# development_board.net
KiCad netlist of a schematic drawn in EAGLE
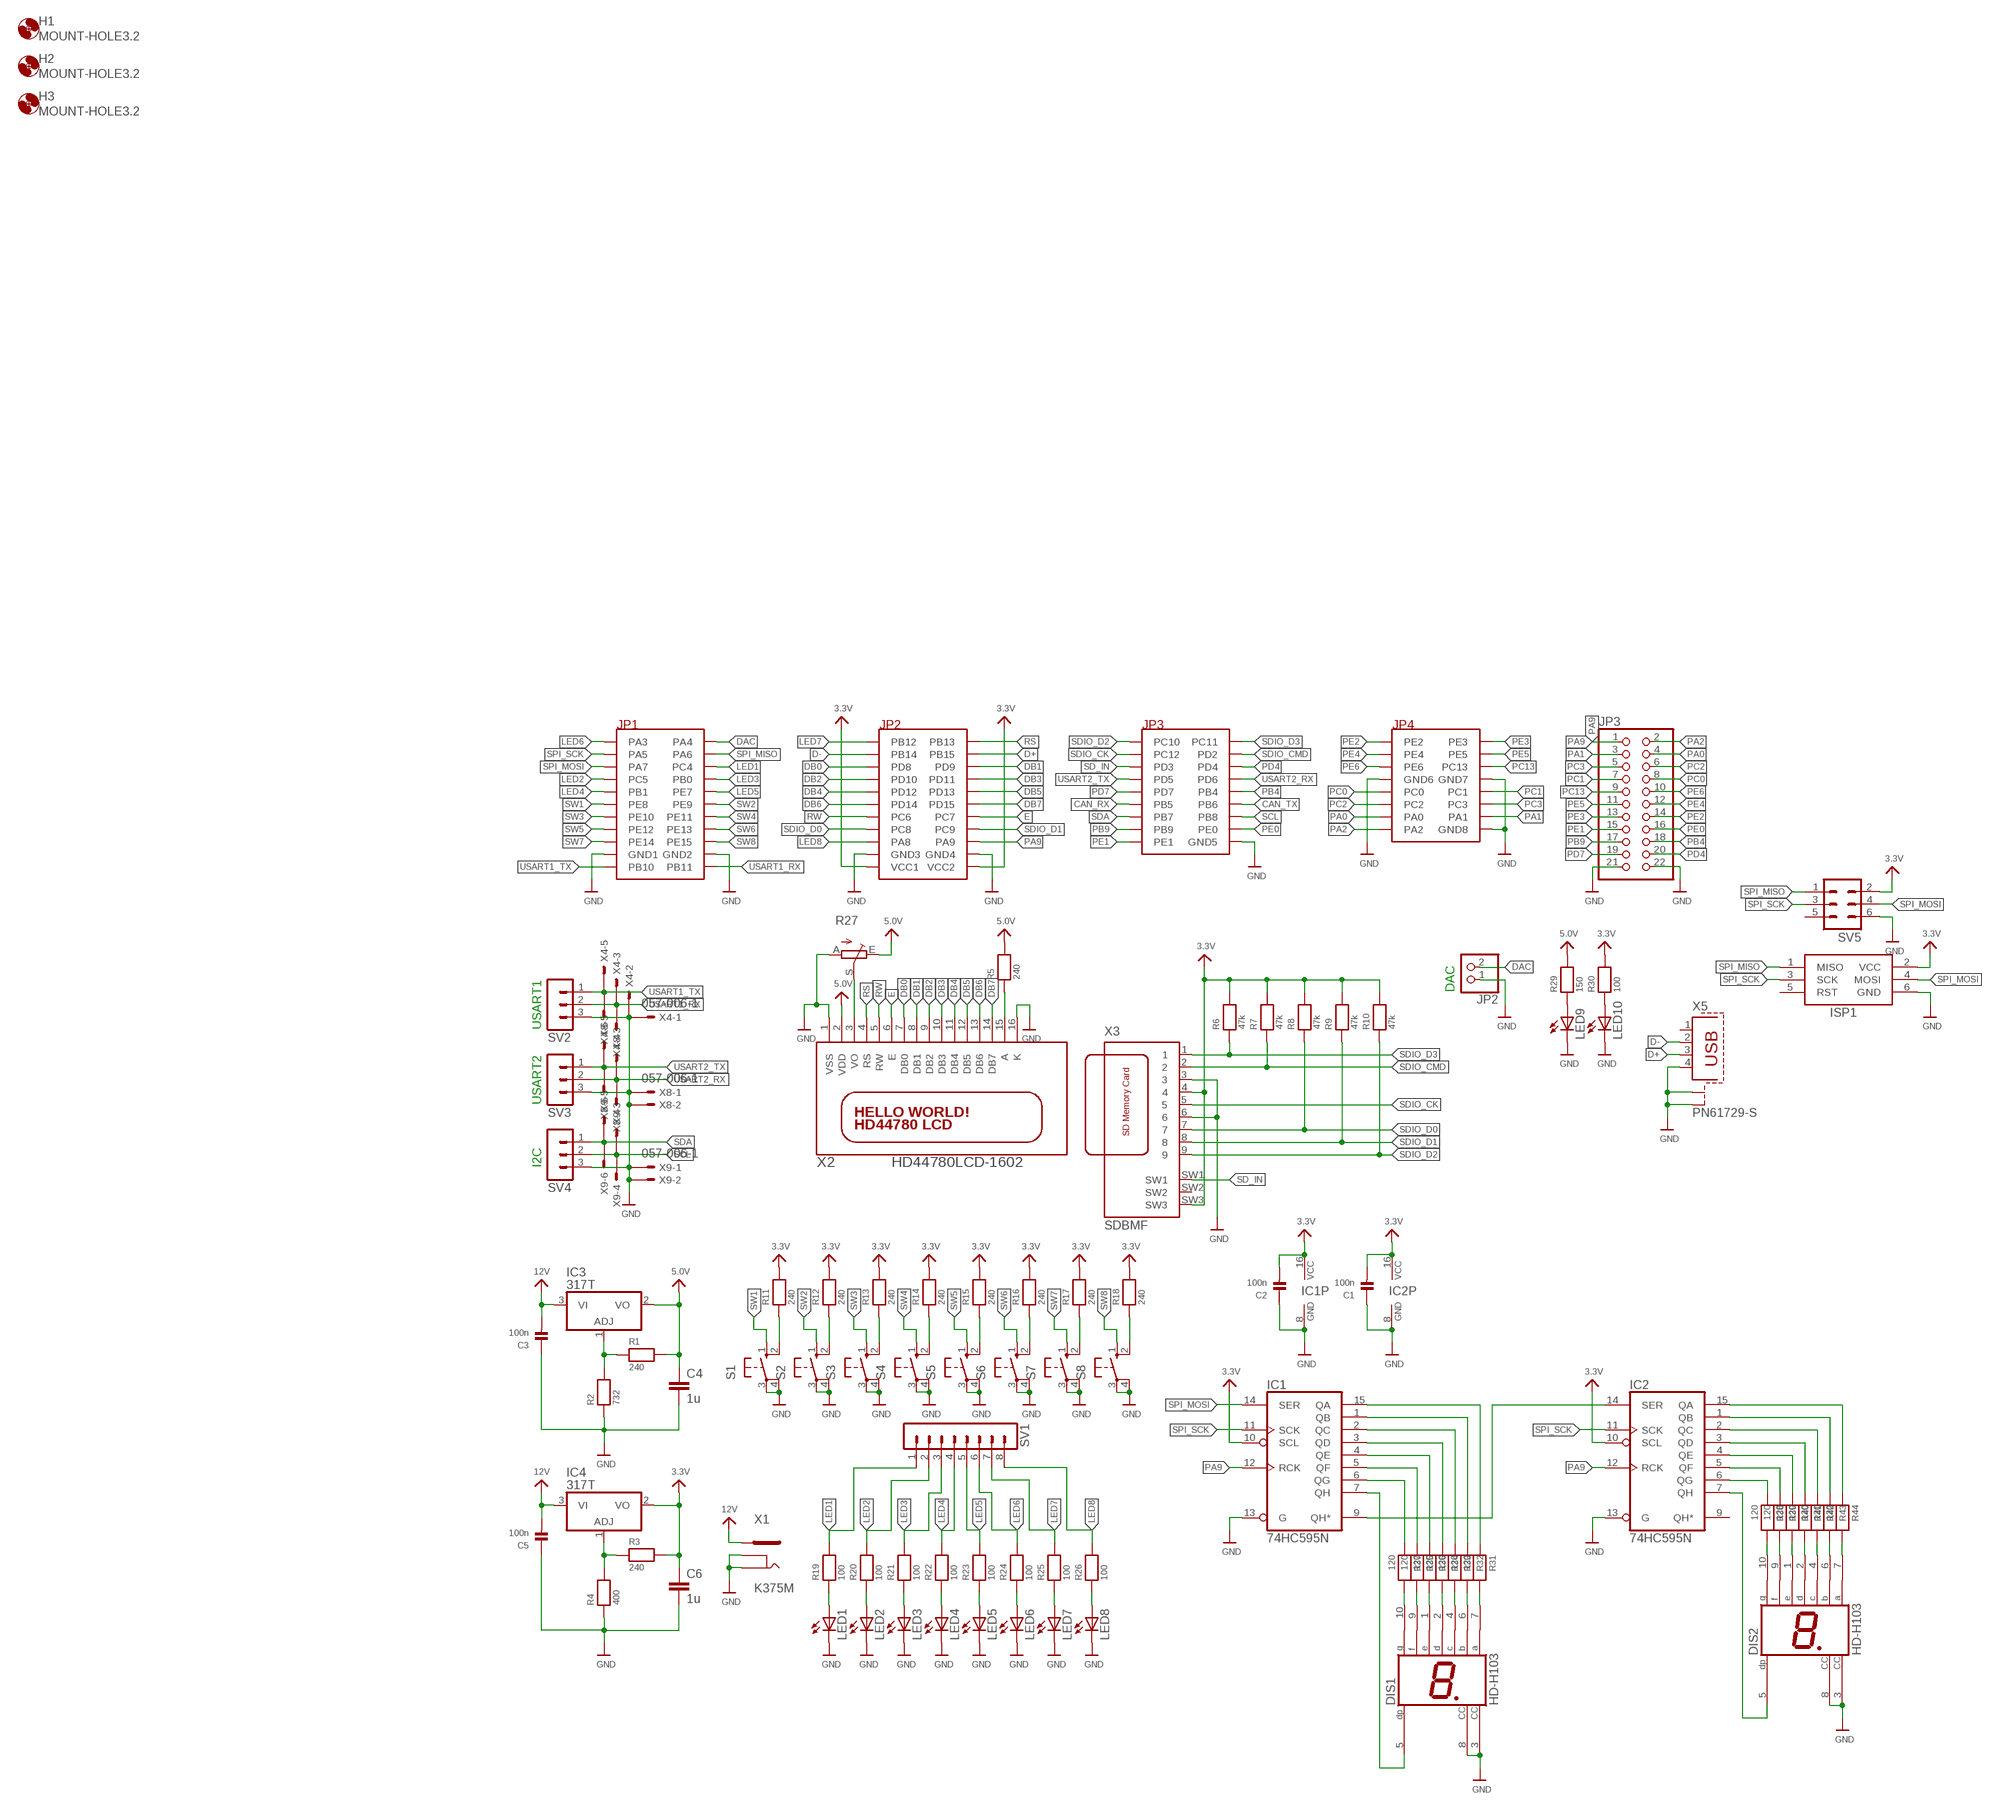
[diagram p0: schematic, sheet 1, part 1 of 2]
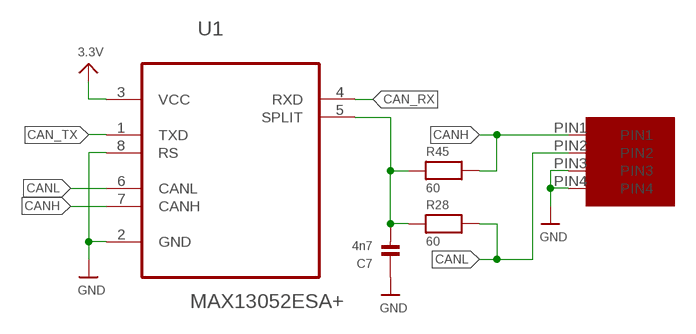
[diagram p1: schematic, sheet 1, part 2 of 2]

(export (version "E")
  (design (tool "Eeschema 10.0.6"))
  (components
    (comp (ref "C1")
      (value "100n")
      (footprint "eagle-import:_0603")
      (libsource (lib "eagle-import") (part "CAP_CERAMIC_0603"))
    )
    (comp (ref "C2")
      (value "100n")
      (footprint "eagle-import:_0603")
      (libsource (lib "eagle-import") (part "CAP_CERAMIC_0603"))
    )
    (comp (ref "C3")
      (value "100n")
      (footprint "eagle-import:_0603")
      (libsource (lib "eagle-import") (part "CAP_CERAMIC_0603"))
    )
    (comp (ref "C4")
      (value "1u")
      (footprint "eagle-import:C050-035X075")
      (libsource (lib "eagle-import") (part "C-EU050-035X075"))
    )
    (comp (ref "C5")
      (value "100n")
      (footprint "eagle-import:_0603")
      (libsource (lib "eagle-import") (part "CAP_CERAMIC_0603"))
    )
    (comp (ref "C6")
      (value "1u")
      (footprint "eagle-import:C050-035X075")
      (libsource (lib "eagle-import") (part "C-EU050-035X075"))
    )
    (comp (ref "C7")
      (value "4n7")
      (footprint "eagle-import:_0603")
      (libsource (lib "eagle-import") (part "CAP_CERAMIC_0603"))
    )
    (comp (ref "DIS1")
      (value "HD-H103")
      (footprint "eagle-import:HDSP-M")
      (libsource (lib "eagle-import") (part "HD-H103"))
    )
    (comp (ref "DIS2")
      (value "HD-H103")
      (footprint "eagle-import:HDSP-M")
      (libsource (lib "eagle-import") (part "HD-H103"))
    )
    (comp (ref "H1")
      (value "MOUNT-HOLE3.2")
      (footprint "eagle-import:3,2")
      (libsource (lib "eagle-import") (part "MOUNT-HOLE3.2"))
    )
    (comp (ref "H2")
      (value "MOUNT-HOLE3.2")
      (footprint "eagle-import:3,2")
      (libsource (lib "eagle-import") (part "MOUNT-HOLE3.2"))
    )
    (comp (ref "H3")
      (value "MOUNT-HOLE3.2")
      (footprint "eagle-import:3,2")
      (libsource (lib "eagle-import") (part "MOUNT-HOLE3.2"))
    )
    (comp (ref "IC1")
      (value "74HC595N")
      (footprint "eagle-import:DIL16")
      (libsource (lib "eagle-import") (part "74595NHC"))
    )
    (comp (ref "IC2")
      (value "74HC595N")
      (footprint "eagle-import:DIL16")
      (libsource (lib "eagle-import") (part "74595NHC"))
    )
    (comp (ref "IC3")
      (value "317T")
      (footprint "eagle-import:TO220H")
      (libsource (lib "eagle-import") (part "317T"))
    )
    (comp (ref "IC4")
      (value "317T")
      (footprint "eagle-import:TO220H")
      (libsource (lib "eagle-import") (part "317T"))
    )
    (comp (ref "ISP1")
      (value "AVRISP-BOX")
      (footprint "eagle-import:AVRISP-BOX")
      (libsource (lib "eagle-import") (part "AVRISP-BOX"))
    )
    (comp (ref "JP2")
      (value "HEADER-1X2ROUND")
      (footprint "eagle-import:1X02_ROUND")
      (libsource (lib "eagle-import") (part "HEADER-1X2ROUND"))
    )
    (comp (ref "JP3")
      (value "PINHD-2X11")
      (footprint "eagle-import:2X11")
      (libsource (lib "eagle-import") (part "PINHD-2X11"))
    )
    (comp (ref "LED1")
      (value "LED5MM")
      (footprint "eagle-import:LED5MM")
      (libsource (lib "eagle-import") (part "LED5MM"))
    )
    (comp (ref "LED2")
      (value "LED5MM")
      (footprint "eagle-import:LED5MM")
      (libsource (lib "eagle-import") (part "LED5MM"))
    )
    (comp (ref "LED3")
      (value "LED5MM")
      (footprint "eagle-import:LED5MM")
      (libsource (lib "eagle-import") (part "LED5MM"))
    )
    (comp (ref "LED4")
      (value "LED5MM")
      (footprint "eagle-import:LED5MM")
      (libsource (lib "eagle-import") (part "LED5MM"))
    )
    (comp (ref "LED5")
      (value "LED5MM")
      (footprint "eagle-import:LED5MM")
      (libsource (lib "eagle-import") (part "LED5MM"))
    )
    (comp (ref "LED6")
      (value "LED5MM")
      (footprint "eagle-import:LED5MM")
      (libsource (lib "eagle-import") (part "LED5MM"))
    )
    (comp (ref "LED7")
      (value "LED5MM")
      (footprint "eagle-import:LED5MM")
      (libsource (lib "eagle-import") (part "LED5MM"))
    )
    (comp (ref "LED8")
      (value "LED5MM")
      (footprint "eagle-import:LED5MM")
      (libsource (lib "eagle-import") (part "LED5MM"))
    )
    (comp (ref "LED9")
      (value "LED3MM")
      (footprint "eagle-import:LED3MM")
      (libsource (lib "eagle-import") (part "led_LED3MM"))
    )
    (comp (ref "LED10")
      (value "LED3MM")
      (footprint "eagle-import:LED3MM")
      (libsource (lib "eagle-import") (part "led_LED3MM"))
    )
    (comp (ref "R1")
      (value "240")
      (footprint "eagle-import:_0603")
      (libsource (lib "eagle-import") (part "RESISTOR_0603"))
    )
    (comp (ref "R2")
      (value "732")
      (footprint "eagle-import:_0603")
      (libsource (lib "eagle-import") (part "RESISTOR_0603"))
    )
    (comp (ref "R3")
      (value "240")
      (footprint "eagle-import:_0603")
      (libsource (lib "eagle-import") (part "RESISTOR_0603"))
    )
    (comp (ref "R4")
      (value "400")
      (footprint "eagle-import:_0603")
      (libsource (lib "eagle-import") (part "RESISTOR_0603"))
    )
    (comp (ref "R5")
      (value "240")
      (footprint "eagle-import:_0603")
      (libsource (lib "eagle-import") (part "RESISTOR_0603"))
    )
    (comp (ref "R6")
      (value "47k")
      (footprint "eagle-import:_0603")
      (libsource (lib "eagle-import") (part "RESISTOR_0603"))
    )
    (comp (ref "R7")
      (value "47k")
      (footprint "eagle-import:_0603")
      (libsource (lib "eagle-import") (part "RESISTOR_0603"))
    )
    (comp (ref "R8")
      (value "47k")
      (footprint "eagle-import:_0603")
      (libsource (lib "eagle-import") (part "RESISTOR_0603"))
    )
    (comp (ref "R9")
      (value "47k")
      (footprint "eagle-import:_0603")
      (libsource (lib "eagle-import") (part "RESISTOR_0603"))
    )
    (comp (ref "R10")
      (value "47k")
      (footprint "eagle-import:_0603")
      (libsource (lib "eagle-import") (part "RESISTOR_0603"))
    )
    (comp (ref "R11")
      (value "240")
      (footprint "eagle-import:_0603")
      (libsource (lib "eagle-import") (part "RESISTOR_0603"))
    )
    (comp (ref "R12")
      (value "240")
      (footprint "eagle-import:_0603")
      (libsource (lib "eagle-import") (part "RESISTOR_0603"))
    )
    (comp (ref "R13")
      (value "240")
      (footprint "eagle-import:_0603")
      (libsource (lib "eagle-import") (part "RESISTOR_0603"))
    )
    (comp (ref "R14")
      (value "240")
      (footprint "eagle-import:_0603")
      (libsource (lib "eagle-import") (part "RESISTOR_0603"))
    )
    (comp (ref "R15")
      (value "240")
      (footprint "eagle-import:_0603")
      (libsource (lib "eagle-import") (part "RESISTOR_0603"))
    )
    (comp (ref "R16")
      (value "240")
      (footprint "eagle-import:_0603")
      (libsource (lib "eagle-import") (part "RESISTOR_0603"))
    )
    (comp (ref "R17")
      (value "240")
      (footprint "eagle-import:_0603")
      (libsource (lib "eagle-import") (part "RESISTOR_0603"))
    )
    (comp (ref "R18")
      (value "240")
      (footprint "eagle-import:_0603")
      (libsource (lib "eagle-import") (part "RESISTOR_0603"))
    )
    (comp (ref "R19")
      (value "100")
      (footprint "eagle-import:_0603")
      (libsource (lib "eagle-import") (part "RESISTOR_0603"))
    )
    (comp (ref "R20")
      (value "100")
      (footprint "eagle-import:_0603")
      (libsource (lib "eagle-import") (part "RESISTOR_0603"))
    )
    (comp (ref "R21")
      (value "100")
      (footprint "eagle-import:_0603")
      (libsource (lib "eagle-import") (part "RESISTOR_0603"))
    )
    (comp (ref "R22")
      (value "100")
      (footprint "eagle-import:_0603")
      (libsource (lib "eagle-import") (part "RESISTOR_0603"))
    )
    (comp (ref "R23")
      (value "100")
      (footprint "eagle-import:_0603")
      (libsource (lib "eagle-import") (part "RESISTOR_0603"))
    )
    (comp (ref "R24")
      (value "100")
      (footprint "eagle-import:_0603")
      (libsource (lib "eagle-import") (part "RESISTOR_0603"))
    )
    (comp (ref "R25")
      (value "100")
      (footprint "eagle-import:_0603")
      (libsource (lib "eagle-import") (part "RESISTOR_0603"))
    )
    (comp (ref "R26")
      (value "100")
      (footprint "eagle-import:_0603")
      (libsource (lib "eagle-import") (part "RESISTOR_0603"))
    )
    (comp (ref "R27")
      (value "TRIM_EU-RJ9W")
      (footprint "eagle-import:RJ9W")
      (libsource (lib "eagle-import") (part "TRIM_EU-RJ9W"))
    )
    (comp (ref "R28")
      (value "60")
      (footprint "eagle-import:_0603")
      (libsource (lib "eagle-import") (part "RESISTOR_0603"))
    )
    (comp (ref "R29")
      (value "150")
      (footprint "eagle-import:_0603")
      (libsource (lib "eagle-import") (part "RESISTOR_0603"))
    )
    (comp (ref "R30")
      (value "100")
      (footprint "eagle-import:_0603")
      (libsource (lib "eagle-import") (part "RESISTOR_0603"))
    )
    (comp (ref "R31")
      (value "120")
      (footprint "eagle-import:_0603")
      (libsource (lib "eagle-import") (part "RESISTOR_0603"))
    )
    (comp (ref "R32")
      (value "120")
      (footprint "eagle-import:_0603")
      (libsource (lib "eagle-import") (part "RESISTOR_0603"))
    )
    (comp (ref "R33")
      (value "120")
      (footprint "eagle-import:_0603")
      (libsource (lib "eagle-import") (part "RESISTOR_0603"))
    )
    (comp (ref "R34")
      (value "120")
      (footprint "eagle-import:_0603")
      (libsource (lib "eagle-import") (part "RESISTOR_0603"))
    )
    (comp (ref "R35")
      (value "120")
      (footprint "eagle-import:_0603")
      (libsource (lib "eagle-import") (part "RESISTOR_0603"))
    )
    (comp (ref "R36")
      (value "120")
      (footprint "eagle-import:_0603")
      (libsource (lib "eagle-import") (part "RESISTOR_0603"))
    )
    (comp (ref "R37")
      (value "120")
      (footprint "eagle-import:_0603")
      (libsource (lib "eagle-import") (part "RESISTOR_0603"))
    )
    (comp (ref "R38")
      (value "120")
      (footprint "eagle-import:_0603")
      (libsource (lib "eagle-import") (part "RESISTOR_0603"))
    )
    (comp (ref "R39")
      (value "120")
      (footprint "eagle-import:_0603")
      (libsource (lib "eagle-import") (part "RESISTOR_0603"))
    )
    (comp (ref "R40")
      (value "120")
      (footprint "eagle-import:_0603")
      (libsource (lib "eagle-import") (part "RESISTOR_0603"))
    )
    (comp (ref "R41")
      (value "120")
      (footprint "eagle-import:_0603")
      (libsource (lib "eagle-import") (part "RESISTOR_0603"))
    )
    (comp (ref "R42")
      (value "120")
      (footprint "eagle-import:_0603")
      (libsource (lib "eagle-import") (part "RESISTOR_0603"))
    )
    (comp (ref "R43")
      (value "120")
      (footprint "eagle-import:_0603")
      (libsource (lib "eagle-import") (part "RESISTOR_0603"))
    )
    (comp (ref "R44")
      (value "120")
      (footprint "eagle-import:_0603")
      (libsource (lib "eagle-import") (part "RESISTOR_0603"))
    )
    (comp (ref "R45")
      (value "60")
      (footprint "eagle-import:_0603")
      (libsource (lib "eagle-import") (part "RESISTOR_0603"))
    )
    (comp (ref "S1")
      (value "10-XX")
      (footprint "eagle-import:B3F-10XX")
      (fields (field (name "MPN") "B3F-1000"))
      (libsource (lib "eagle-import") (part "10-XX"))
    )
    (comp (ref "S2")
      (value "10-XX")
      (footprint "eagle-import:B3F-10XX")
      (fields (field (name "MPN") "B3F-1000"))
      (libsource (lib "eagle-import") (part "10-XX"))
    )
    (comp (ref "S3")
      (value "10-XX")
      (footprint "eagle-import:B3F-10XX")
      (fields (field (name "MPN") "B3F-1000"))
      (libsource (lib "eagle-import") (part "10-XX"))
    )
    (comp (ref "S4")
      (value "10-XX")
      (footprint "eagle-import:B3F-10XX")
      (fields (field (name "MPN") "B3F-1000"))
      (libsource (lib "eagle-import") (part "10-XX"))
    )
    (comp (ref "S5")
      (value "10-XX")
      (footprint "eagle-import:B3F-10XX")
      (fields (field (name "MPN") "B3F-1000"))
      (libsource (lib "eagle-import") (part "10-XX"))
    )
    (comp (ref "S6")
      (value "10-XX")
      (footprint "eagle-import:B3F-10XX")
      (fields (field (name "MPN") "B3F-1000"))
      (libsource (lib "eagle-import") (part "10-XX"))
    )
    (comp (ref "S7")
      (value "10-XX")
      (footprint "eagle-import:B3F-10XX")
      (fields (field (name "MPN") "B3F-1000"))
      (libsource (lib "eagle-import") (part "10-XX"))
    )
    (comp (ref "S8")
      (value "10-XX")
      (footprint "eagle-import:B3F-10XX")
      (fields (field (name "MPN") "B3F-1000"))
      (libsource (lib "eagle-import") (part "10-XX"))
    )
    (comp (ref "SV1")
      (value "MA08-1")
      (footprint "eagle-import:MA08-1")
      (libsource (lib "eagle-import") (part "MA08-1"))
    )
    (comp (ref "SV2")
      (value "MA03-1")
      (footprint "eagle-import:MA03-1")
      (libsource (lib "eagle-import") (part "MA03-1"))
    )
    (comp (ref "SV3")
      (value "MA03-1")
      (footprint "eagle-import:MA03-1")
      (libsource (lib "eagle-import") (part "MA03-1"))
    )
    (comp (ref "SV4")
      (value "MA03-1")
      (footprint "eagle-import:MA03-1")
      (libsource (lib "eagle-import") (part "MA03-1"))
    )
    (comp (ref "SV5")
      (value "MA03-2")
      (footprint "eagle-import:MA03-2")
      (libsource (lib "eagle-import") (part "MA03-2"))
    )
    (comp (ref "U$1")
      (value "CPU-BOARD")
      (footprint "eagle-import:CPU-BOARD-JP1")
      (libsource (lib "eagle-import") (part "CPU-BOARD"))
    )
    (comp (ref "U$57")
      (value "MICROFIT4")
      (footprint "eagle-import:MICROFIT4SOCK")
      (libsource (lib "eagle-import") (part "MICROFIT4"))
    )
    (comp (ref "U1")
      (value "MAX13052ESA+")
      (footprint "eagle-import:SOIC127P600X175-8N")
      (libsource (lib "eagle-import") (part "MAX13052ESA+"))
    )
    (comp (ref "X1")
      (value "K375M")
      (footprint "eagle-import:K375M")
      (libsource (lib "eagle-import") (part "K375M"))
    )
    (comp (ref "X2")
      (value "HD44780LCD-1602")
      (footprint "eagle-import:LCD1602")
      (libsource (lib "eagle-import") (part "HD44780LCD-1602"))
    )
    (comp (ref "X3")
      (value "SDBMF")
      (footprint "eagle-import:SDBMF-009XXBXX2")
      (libsource (lib "eagle-import") (part "SDBMF"))
    )
    (comp (ref "X4")
      (value "057-006-1")
      (footprint "eagle-import:057-006-1")
      (fields (field (name "OC_FARNELL") "unknown") (field (name "OC_NEWARK") "unknown"))
      (libsource (lib "eagle-import") (part "057-006-1"))
    )
    (comp (ref "X5")
      (value "PN61729-S")
      (footprint "eagle-import:PN61729-S")
      (libsource (lib "eagle-import") (part "PN61729-S"))
    )
    (comp (ref "X8")
      (value "057-006-1")
      (footprint "eagle-import:057-006-1")
      (fields (field (name "OC_FARNELL") "unknown") (field (name "OC_NEWARK") "unknown"))
      (libsource (lib "eagle-import") (part "057-006-1"))
    )
    (comp (ref "X9")
      (value "057-006-1")
      (footprint "eagle-import:057-006-1")
      (fields (field (name "OC_FARNELL") "unknown") (field (name "OC_NEWARK") "unknown"))
      (libsource (lib "eagle-import") (part "057-006-1"))
    )
  )
  (nets
    (net (code "1") (name "3.3V") (class "Default")
      (node (ref "C1") (pin "2") (pinfunction "P$2_2") (pintype "passive"))
      (node (ref "C2") (pin "2") (pinfunction "P$2_2") (pintype "passive"))
      (node (ref "C6") (pin "1") (pinfunction "1_1") (pintype "passive"))
      (node (ref "IC1") (pin "10") (pinfunction "SCL_10") (pintype "input"))
      (node (ref "IC1") (pin "16") (pinfunction "VCC_16") (pintype "power_in"))
      (node (ref "IC2") (pin "10") (pinfunction "SCL_10") (pintype "input"))
      (node (ref "IC2") (pin "16") (pinfunction "VCC_16") (pintype "power_in"))
      (node (ref "IC4") (pin "2") (pinfunction "VO_2") (pintype "passive"))
      (node (ref "ISP1") (pin "2") (pinfunction "VCC_2") (pintype "power_in"))
      (node (ref "R10") (pin "2") (pinfunction "2_2") (pintype "passive"))
      (node (ref "R11") (pin "2") (pinfunction "2_2") (pintype "passive"))
      (node (ref "R12") (pin "2") (pinfunction "2_2") (pintype "passive"))
      (node (ref "R13") (pin "2") (pinfunction "2_2") (pintype "passive"))
      (node (ref "R14") (pin "2") (pinfunction "2_2") (pintype "passive"))
      (node (ref "R15") (pin "2") (pinfunction "2_2") (pintype "passive"))
      (node (ref "R16") (pin "2") (pinfunction "2_2") (pintype "passive"))
      (node (ref "R17") (pin "2") (pinfunction "2_2") (pintype "passive"))
      (node (ref "R18") (pin "2") (pinfunction "2_2") (pintype "passive"))
      (node (ref "R3") (pin "2") (pinfunction "2_2") (pintype "passive"))
      (node (ref "R30") (pin "2") (pinfunction "2_2") (pintype "passive"))
      (node (ref "R6") (pin "2") (pinfunction "2_2") (pintype "passive"))
      (node (ref "R7") (pin "2") (pinfunction "2_2") (pintype "passive"))
      (node (ref "R8") (pin "2") (pinfunction "2_2") (pintype "passive"))
      (node (ref "R9") (pin "2") (pinfunction "2_2") (pintype "passive"))
      (node (ref "SV5") (pin "2") (pinfunction "2_2") (pintype "passive"))
      (node (ref "U$1") (pin "P$43") (pinfunction "VCC1_P$43") (pintype "bidirectional"))
      (node (ref "U$1") (pin "P$44") (pinfunction "VCC2_P$44") (pintype "bidirectional"))
      (node (ref "U1") (pin "3") (pinfunction "VCC_3") (pintype "power_in"))
      (node (ref "X3") (pin "4") (pinfunction "4_4") (pintype "passive"))
      (node (ref "X3") (pin "SW3") (pinfunction "SW3_SW3") (pintype "passive"))
    )
    (net (code "2") (name "5.0V") (class "Default")
      (node (ref "C4") (pin "1") (pinfunction "1_1") (pintype "passive"))
      (node (ref "IC3") (pin "2") (pinfunction "VO_2") (pintype "passive"))
      (node (ref "R1") (pin "2") (pinfunction "2_2") (pintype "passive"))
      (node (ref "R27") (pin "E") (pinfunction "E_E") (pintype "passive"))
      (node (ref "R29") (pin "2") (pinfunction "2_2") (pintype "passive"))
      (node (ref "R5") (pin "2") (pinfunction "2_2") (pintype "passive"))
      (node (ref "X2") (pin "2") (pinfunction "VDD_2") (pintype "power_in"))
    )
    (net (code "3") (name "12V") (class "Default")
      (node (ref "C3") (pin "2") (pinfunction "P$2_2") (pintype "passive"))
      (node (ref "C5") (pin "2") (pinfunction "P$2_2") (pintype "passive"))
      (node (ref "IC3") (pin "3") (pinfunction "VI_3") (pintype "input"))
      (node (ref "IC4") (pin "3") (pinfunction "VI_3") (pintype "input"))
      (node (ref "X1") (pin "1") (pinfunction "1_1") (pintype "passive"))
    )
    (net (code "4") (name "CANH") (class "Default")
      (node (ref "R45") (pin "2") (pinfunction "2_2") (pintype "passive"))
      (node (ref "U$57") (pin "PIN1") (pinfunction "PIN1_PIN1") (pintype "bidirectional"))
      (node (ref "U1") (pin "7") (pinfunction "CANH_7") (pintype "input"))
    )
    (net (code "5") (name "CANL") (class "Default")
      (node (ref "R28") (pin "2") (pinfunction "2_2") (pintype "passive"))
      (node (ref "U$57") (pin "PIN2") (pinfunction "PIN2_PIN2") (pintype "bidirectional"))
      (node (ref "U1") (pin "6") (pinfunction "CANL_6") (pintype "input"))
    )
    (net (code "6") (name "CAN_RX") (class "Default")
      (node (ref "U$1") (pin "P$55") (pinfunction "PB5_P$55") (pintype "bidirectional"))
      (node (ref "U1") (pin "4") (pinfunction "RXD_4") (pintype "output"))
    )
    (net (code "7") (name "CAN_TX") (class "Default")
      (node (ref "U$1") (pin "P$56") (pinfunction "PB6_P$56") (pintype "bidirectional"))
      (node (ref "U1") (pin "1") (pinfunction "TXD_1") (pintype "input"))
    )
    (net (code "8") (name "D+") (class "Default")
      (node (ref "U$1") (pin "P$26") (pinfunction "PB15_P$26") (pintype "bidirectional"))
      (node (ref "X5") (pin "3") (pinfunction "3_3") (pintype "passive"))
    )
    (net (code "9") (name "D-") (class "Default")
      (node (ref "U$1") (pin "P$25") (pinfunction "PB14_P$25") (pintype "bidirectional"))
      (node (ref "X5") (pin "2") (pinfunction "2_2") (pintype "passive"))
    )
    (net (code "10") (name "DAC") (class "Default")
      (node (ref "JP2") (pin "2") (pinfunction "2_2") (pintype "passive"))
      (node (ref "U$1") (pin "P$2") (pinfunction "PA4_P$2") (pintype "bidirectional"))
    )
    (net (code "11") (name "DB0") (class "Default")
      (node (ref "U$1") (pin "P$27") (pinfunction "PD8_P$27") (pintype "bidirectional"))
      (node (ref "X2") (pin "7") (pinfunction "DB0_7") (pintype "bidirectional"))
    )
    (net (code "12") (name "DB1") (class "Default")
      (node (ref "U$1") (pin "P$28") (pinfunction "PD9_P$28") (pintype "bidirectional"))
      (node (ref "X2") (pin "8") (pinfunction "DB1_8") (pintype "bidirectional"))
    )
    (net (code "13") (name "DB2") (class "Default")
      (node (ref "U$1") (pin "P$29") (pinfunction "PD10_P$29") (pintype "bidirectional"))
      (node (ref "X2") (pin "9") (pinfunction "DB2_9") (pintype "bidirectional"))
    )
    (net (code "14") (name "DB3") (class "Default")
      (node (ref "U$1") (pin "P$30") (pinfunction "PD11_P$30") (pintype "bidirectional"))
      (node (ref "X2") (pin "10") (pinfunction "DB3_10") (pintype "bidirectional"))
    )
    (net (code "15") (name "DB4") (class "Default")
      (node (ref "U$1") (pin "P$31") (pinfunction "PD12_P$31") (pintype "bidirectional"))
      (node (ref "X2") (pin "11") (pinfunction "DB4_11") (pintype "bidirectional"))
    )
    (net (code "16") (name "DB5") (class "Default")
      (node (ref "U$1") (pin "P$32") (pinfunction "PD13_P$32") (pintype "bidirectional"))
      (node (ref "X2") (pin "12") (pinfunction "DB5_12") (pintype "bidirectional"))
    )
    (net (code "17") (name "DB6") (class "Default")
      (node (ref "U$1") (pin "P$33") (pinfunction "PD14_P$33") (pintype "bidirectional"))
      (node (ref "X2") (pin "13") (pinfunction "DB6_13") (pintype "bidirectional"))
    )
    (net (code "18") (name "DB7") (class "Default")
      (node (ref "U$1") (pin "P$34") (pinfunction "PD15_P$34") (pintype "bidirectional"))
      (node (ref "X2") (pin "14") (pinfunction "DB7_14") (pintype "bidirectional"))
    )
    (net (code "19") (name "E") (class "Default")
      (node (ref "U$1") (pin "P$36") (pinfunction "PC7_P$36") (pintype "bidirectional"))
      (node (ref "X2") (pin "6") (pinfunction "E_6") (pintype "input"))
    )
    (net (code "20") (name "GND") (class "Default")
      (node (ref "C1") (pin "1") (pinfunction "P$1_1") (pintype "passive"))
      (node (ref "C2") (pin "1") (pinfunction "P$1_1") (pintype "passive"))
      (node (ref "C3") (pin "1") (pinfunction "P$1_1") (pintype "passive"))
      (node (ref "C4") (pin "2") (pinfunction "2_2") (pintype "passive"))
      (node (ref "C5") (pin "1") (pinfunction "P$1_1") (pintype "passive"))
      (node (ref "C6") (pin "2") (pinfunction "2_2") (pintype "passive"))
      (node (ref "C7") (pin "1") (pinfunction "P$1_1") (pintype "passive"))
      (node (ref "DIS1") (pin "3") (pinfunction "CC_3") (pintype "passive"))
      (node (ref "DIS1") (pin "8") (pinfunction "CC_8") (pintype "passive"))
      (node (ref "DIS2") (pin "3") (pinfunction "CC_3") (pintype "passive"))
      (node (ref "DIS2") (pin "8") (pinfunction "CC_8") (pintype "passive"))
      (node (ref "IC1") (pin "13") (pinfunction "G_13") (pintype "input"))
      (node (ref "IC1") (pin "8") (pinfunction "GND_8") (pintype "power_in"))
      (node (ref "IC2") (pin "13") (pinfunction "G_13") (pintype "input"))
      (node (ref "IC2") (pin "8") (pinfunction "GND_8") (pintype "power_in"))
      (node (ref "ISP1") (pin "6") (pinfunction "GND_6") (pintype "power_in"))
      (node (ref "JP2") (pin "1") (pinfunction "1_1") (pintype "passive"))
      (node (ref "JP3") (pin "21") (pinfunction "21_21") (pintype "passive"))
      (node (ref "JP3") (pin "22") (pinfunction "22_22") (pintype "passive"))
      (node (ref "LED1") (pin "K") (pinfunction "C_K") (pintype "passive"))
      (node (ref "LED10") (pin "K") (pinfunction "C_K") (pintype "passive"))
      (node (ref "LED2") (pin "K") (pinfunction "C_K") (pintype "passive"))
      (node (ref "LED3") (pin "K") (pinfunction "C_K") (pintype "passive"))
      (node (ref "LED4") (pin "K") (pinfunction "C_K") (pintype "passive"))
      (node (ref "LED5") (pin "K") (pinfunction "C_K") (pintype "passive"))
      (node (ref "LED6") (pin "K") (pinfunction "C_K") (pintype "passive"))
      (node (ref "LED7") (pin "K") (pinfunction "C_K") (pintype "passive"))
      (node (ref "LED8") (pin "K") (pinfunction "C_K") (pintype "passive"))
      (node (ref "LED9") (pin "K") (pinfunction "C_K") (pintype "passive"))
      (node (ref "R2") (pin "1") (pinfunction "1_1") (pintype "passive"))
      (node (ref "R27") (pin "A") (pinfunction "A_A") (pintype "passive"))
      (node (ref "R4") (pin "1") (pinfunction "1_1") (pintype "passive"))
      (node (ref "S1") (pin "3") (pinfunction "P_3") (pintype "passive"))
      (node (ref "S1") (pin "4") (pinfunction "P1_4") (pintype "passive"))
      (node (ref "S2") (pin "3") (pinfunction "P_3") (pintype "passive"))
      (node (ref "S2") (pin "4") (pinfunction "P1_4") (pintype "passive"))
      (node (ref "S3") (pin "3") (pinfunction "P_3") (pintype "passive"))
      (node (ref "S3") (pin "4") (pinfunction "P1_4") (pintype "passive"))
      (node (ref "S4") (pin "3") (pinfunction "P_3") (pintype "passive"))
      (node (ref "S4") (pin "4") (pinfunction "P1_4") (pintype "passive"))
      (node (ref "S5") (pin "3") (pinfunction "P_3") (pintype "passive"))
      (node (ref "S5") (pin "4") (pinfunction "P1_4") (pintype "passive"))
      (node (ref "S6") (pin "3") (pinfunction "P_3") (pintype "passive"))
      (node (ref "S6") (pin "4") (pinfunction "P1_4") (pintype "passive"))
      (node (ref "S7") (pin "3") (pinfunction "P_3") (pintype "passive"))
      (node (ref "S7") (pin "4") (pinfunction "P1_4") (pintype "passive"))
      (node (ref "S8") (pin "3") (pinfunction "P_3") (pintype "passive"))
      (node (ref "S8") (pin "4") (pinfunction "P1_4") (pintype "passive"))
      (node (ref "SV2") (pin "3") (pinfunction "3_3") (pintype "passive"))
      (node (ref "SV3") (pin "3") (pinfunction "3_3") (pintype "passive"))
      (node (ref "SV4") (pin "3") (pinfunction "3_3") (pintype "passive"))
      (node (ref "SV5") (pin "6") (pinfunction "6_6") (pintype "passive"))
      (node (ref "U$1") (pin "P$21") (pinfunction "GND1_P$21") (pintype "bidirectional"))
      (node (ref "U$1") (pin "P$22") (pinfunction "GND2_P$22") (pintype "bidirectional"))
      (node (ref "U$1") (pin "P$41") (pinfunction "GND3_P$41") (pintype "bidirectional"))
      (node (ref "U$1") (pin "P$42") (pinfunction "GND4_P$42") (pintype "bidirectional"))
      (node (ref "U$1") (pin "P$62") (pinfunction "GND5_P$62") (pintype "bidirectional"))
      (node (ref "U$1") (pin "P$69") (pinfunction "GND6_P$69") (pintype "bidirectional"))
      (node (ref "U$1") (pin "P$70") (pinfunction "GND7_P$70") (pintype "bidirectional"))
      (node (ref "U$1") (pin "P$78") (pinfunction "GND8_P$78") (pintype "bidirectional"))
      (node (ref "U$57") (pin "PIN3") (pinfunction "PIN3_PIN3") (pintype "bidirectional"))
      (node (ref "U$57") (pin "PIN4") (pinfunction "PIN4_PIN4") (pintype "bidirectional"))
      (node (ref "U1") (pin "2") (pinfunction "GND_2") (pintype "passive"))
      (node (ref "U1") (pin "8") (pinfunction "RS_8") (pintype "input"))
      (node (ref "X1") (pin "2") (pinfunction "2_2") (pintype "passive"))
      (node (ref "X1") (pin "3") (pinfunction "3_3") (pintype "passive"))
      (node (ref "X2") (pin "1") (pinfunction "VSS_1") (pintype "power_in"))
      (node (ref "X2") (pin "16") (pinfunction "K_16") (pintype "input"))
      (node (ref "X3") (pin "3") (pinfunction "3_3") (pintype "passive"))
      (node (ref "X3") (pin "6") (pinfunction "6_6") (pintype "passive"))
      (node (ref "X4") (pin "1") (pinfunction "S_1") (pintype "passive"))
      (node (ref "X4") (pin "2") (pinfunction "S_2") (pintype "passive"))
      (node (ref "X5") (pin "4") (pinfunction "4_4") (pintype "passive"))
      (node (ref "X5") (pin "S1") (pinfunction "S1_S1") (pintype "passive"))
      (node (ref "X5") (pin "S2") (pinfunction "S2_S2") (pintype "passive"))
      (node (ref "X8") (pin "1") (pinfunction "S_1") (pintype "passive"))
      (node (ref "X8") (pin "2") (pinfunction "S_2") (pintype "passive"))
      (node (ref "X9") (pin "1") (pinfunction "S_1") (pintype "passive"))
      (node (ref "X9") (pin "2") (pinfunction "S_2") (pintype "passive"))
    )
    (net (code "21") (name "LED1") (class "Default")
      (node (ref "R19") (pin "2") (pinfunction "2_2") (pintype "passive"))
      (node (ref "SV1") (pin "1") (pinfunction "1_1") (pintype "passive"))
      (node (ref "U$1") (pin "P$6") (pinfunction "PC4_P$6") (pintype "bidirectional"))
    )
    (net (code "22") (name "LED2") (class "Default")
      (node (ref "R20") (pin "2") (pinfunction "2_2") (pintype "passive"))
      (node (ref "SV1") (pin "2") (pinfunction "2_2") (pintype "passive"))
      (node (ref "U$1") (pin "P$7") (pinfunction "PC5_P$7") (pintype "bidirectional"))
    )
    (net (code "23") (name "LED3") (class "Default")
      (node (ref "R21") (pin "2") (pinfunction "2_2") (pintype "passive"))
      (node (ref "SV1") (pin "3") (pinfunction "3_3") (pintype "passive"))
      (node (ref "U$1") (pin "P$8") (pinfunction "PB0_P$8") (pintype "bidirectional"))
    )
    (net (code "24") (name "LED4") (class "Default")
      (node (ref "R22") (pin "2") (pinfunction "2_2") (pintype "passive"))
      (node (ref "SV1") (pin "4") (pinfunction "4_4") (pintype "passive"))
      (node (ref "U$1") (pin "P$9") (pinfunction "PB1_P$9") (pintype "bidirectional"))
    )
    (net (code "25") (name "LED5") (class "Default")
      (node (ref "R23") (pin "2") (pinfunction "2_2") (pintype "passive"))
      (node (ref "SV1") (pin "5") (pinfunction "5_5") (pintype "passive"))
      (node (ref "U$1") (pin "P$10") (pinfunction "PE7_P$10") (pintype "bidirectional"))
    )
    (net (code "26") (name "LED6") (class "Default")
      (node (ref "R24") (pin "2") (pinfunction "2_2") (pintype "passive"))
      (node (ref "SV1") (pin "6") (pinfunction "6_6") (pintype "passive"))
      (node (ref "U$1") (pin "P$1") (pinfunction "PA3_P$1") (pintype "bidirectional"))
    )
    (net (code "27") (name "LED7") (class "Default")
      (node (ref "R25") (pin "2") (pinfunction "2_2") (pintype "passive"))
      (node (ref "SV1") (pin "7") (pinfunction "7_7") (pintype "passive"))
      (node (ref "U$1") (pin "P$23") (pinfunction "PB12_P$23") (pintype "bidirectional"))
    )
    (net (code "28") (name "LED8") (class "Default")
      (node (ref "R26") (pin "2") (pinfunction "2_2") (pintype "passive"))
      (node (ref "SV1") (pin "8") (pinfunction "8_8") (pintype "passive"))
      (node (ref "U$1") (pin "P$39") (pinfunction "PA8_P$39") (pintype "bidirectional"))
    )
    (net (code "29") (name "Net-(C7-P$2)") (class "Default")
      (node (ref "C7") (pin "2") (pinfunction "P$2_2") (pintype "passive"))
      (node (ref "R28") (pin "1") (pinfunction "1_1") (pintype "passive"))
      (node (ref "R45") (pin "1") (pinfunction "1_1") (pintype "passive"))
      (node (ref "U1") (pin "5") (pinfunction "SPLIT_5") (pintype "output"))
    )
    (net (code "30") (name "Net-(DIS1-A)") (class "Default")
      (node (ref "DIS1") (pin "7") (pinfunction "A_7") (pintype "passive"))
      (node (ref "R31") (pin "2") (pinfunction "2_2") (pintype "passive"))
    )
    (net (code "31") (name "Net-(DIS1-B)") (class "Default")
      (node (ref "DIS1") (pin "6") (pinfunction "B_6") (pintype "passive"))
      (node (ref "R32") (pin "2") (pinfunction "2_2") (pintype "passive"))
    )
    (net (code "32") (name "Net-(DIS1-C)") (class "Default")
      (node (ref "DIS1") (pin "4") (pinfunction "C_4") (pintype "passive"))
      (node (ref "R33") (pin "2") (pinfunction "2_2") (pintype "passive"))
    )
    (net (code "33") (name "Net-(DIS1-D)") (class "Default")
      (node (ref "DIS1") (pin "2") (pinfunction "D_2") (pintype "passive"))
      (node (ref "R34") (pin "2") (pinfunction "2_2") (pintype "passive"))
    )
    (net (code "34") (name "Net-(DIS1-DP)") (class "Default")
      (node (ref "DIS1") (pin "5") (pinfunction "DP_5") (pintype "passive"))
      (node (ref "IC1") (pin "7") (pinfunction "QH_7") (pintype "tri_state"))
    )
    (net (code "35") (name "Net-(DIS1-E)") (class "Default")
      (node (ref "DIS1") (pin "1") (pinfunction "E_1") (pintype "passive"))
      (node (ref "R36") (pin "2") (pinfunction "2_2") (pintype "passive"))
    )
    (net (code "36") (name "Net-(DIS1-F)") (class "Default")
      (node (ref "DIS1") (pin "9") (pinfunction "F_9") (pintype "passive"))
      (node (ref "R35") (pin "2") (pinfunction "2_2") (pintype "passive"))
    )
    (net (code "37") (name "Net-(DIS1-G)") (class "Default")
      (node (ref "DIS1") (pin "10") (pinfunction "G_10") (pintype "passive"))
      (node (ref "R37") (pin "2") (pinfunction "2_2") (pintype "passive"))
    )
    (net (code "38") (name "Net-(DIS2-A)") (class "Default")
      (node (ref "DIS2") (pin "7") (pinfunction "A_7") (pintype "passive"))
      (node (ref "R44") (pin "2") (pinfunction "2_2") (pintype "passive"))
    )
    (net (code "39") (name "Net-(DIS2-B)") (class "Default")
      (node (ref "DIS2") (pin "6") (pinfunction "B_6") (pintype "passive"))
      (node (ref "R43") (pin "2") (pinfunction "2_2") (pintype "passive"))
    )
    (net (code "40") (name "Net-(DIS2-C)") (class "Default")
      (node (ref "DIS2") (pin "4") (pinfunction "C_4") (pintype "passive"))
      (node (ref "R42") (pin "2") (pinfunction "2_2") (pintype "passive"))
    )
    (net (code "41") (name "Net-(DIS2-D)") (class "Default")
      (node (ref "DIS2") (pin "2") (pinfunction "D_2") (pintype "passive"))
      (node (ref "R41") (pin "2") (pinfunction "2_2") (pintype "passive"))
    )
    (net (code "42") (name "Net-(DIS2-DP)") (class "Default")
      (node (ref "DIS2") (pin "5") (pinfunction "DP_5") (pintype "passive"))
      (node (ref "IC2") (pin "7") (pinfunction "QH_7") (pintype "tri_state"))
    )
    (net (code "43") (name "Net-(DIS2-E)") (class "Default")
      (node (ref "DIS2") (pin "1") (pinfunction "E_1") (pintype "passive"))
      (node (ref "R40") (pin "2") (pinfunction "2_2") (pintype "passive"))
    )
    (net (code "44") (name "Net-(DIS2-F)") (class "Default")
      (node (ref "DIS2") (pin "9") (pinfunction "F_9") (pintype "passive"))
      (node (ref "R39") (pin "2") (pinfunction "2_2") (pintype "passive"))
    )
    (net (code "45") (name "Net-(DIS2-G)") (class "Default")
      (node (ref "DIS2") (pin "10") (pinfunction "G_10") (pintype "passive"))
      (node (ref "R38") (pin "2") (pinfunction "2_2") (pintype "passive"))
    )
    (net (code "46") (name "Net-(IC1A-QA)") (class "Default")
      (node (ref "IC1") (pin "15") (pinfunction "QA_15") (pintype "tri_state"))
      (node (ref "R31") (pin "1") (pinfunction "1_1") (pintype "passive"))
    )
    (net (code "47") (name "Net-(IC1A-QB)") (class "Default")
      (node (ref "IC1") (pin "1") (pinfunction "QB_1") (pintype "tri_state"))
      (node (ref "R32") (pin "1") (pinfunction "1_1") (pintype "passive"))
    )
    (net (code "48") (name "Net-(IC1A-QC)") (class "Default")
      (node (ref "IC1") (pin "2") (pinfunction "QC_2") (pintype "tri_state"))
      (node (ref "R33") (pin "1") (pinfunction "1_1") (pintype "passive"))
    )
    (net (code "49") (name "Net-(IC1A-QD)") (class "Default")
      (node (ref "IC1") (pin "3") (pinfunction "QD_3") (pintype "tri_state"))
      (node (ref "R34") (pin "1") (pinfunction "1_1") (pintype "passive"))
    )
    (net (code "50") (name "Net-(IC1A-QE)") (class "Default")
      (node (ref "IC1") (pin "4") (pinfunction "QE_4") (pintype "tri_state"))
      (node (ref "R36") (pin "1") (pinfunction "1_1") (pintype "passive"))
    )
    (net (code "51") (name "Net-(IC1A-QF)") (class "Default")
      (node (ref "IC1") (pin "5") (pinfunction "QF_5") (pintype "tri_state"))
      (node (ref "R35") (pin "1") (pinfunction "1_1") (pintype "passive"))
    )
    (net (code "52") (name "Net-(IC1A-QG)") (class "Default")
      (node (ref "IC1") (pin "6") (pinfunction "QG_6") (pintype "tri_state"))
      (node (ref "R37") (pin "1") (pinfunction "1_1") (pintype "passive"))
    )
    (net (code "53") (name "Net-(IC1A-QH*)") (class "Default")
      (node (ref "IC1") (pin "9") (pinfunction "QH*_9") (pintype "tri_state"))
      (node (ref "IC2") (pin "14") (pinfunction "SER_14") (pintype "input"))
    )
    (net (code "54") (name "Net-(IC2A-QA)") (class "Default")
      (node (ref "IC2") (pin "15") (pinfunction "QA_15") (pintype "tri_state"))
      (node (ref "R44") (pin "1") (pinfunction "1_1") (pintype "passive"))
    )
    (net (code "55") (name "Net-(IC2A-QB)") (class "Default")
      (node (ref "IC2") (pin "1") (pinfunction "QB_1") (pintype "tri_state"))
      (node (ref "R43") (pin "1") (pinfunction "1_1") (pintype "passive"))
    )
    (net (code "56") (name "Net-(IC2A-QC)") (class "Default")
      (node (ref "IC2") (pin "2") (pinfunction "QC_2") (pintype "tri_state"))
      (node (ref "R42") (pin "1") (pinfunction "1_1") (pintype "passive"))
    )
    (net (code "57") (name "Net-(IC2A-QD)") (class "Default")
      (node (ref "IC2") (pin "3") (pinfunction "QD_3") (pintype "tri_state"))
      (node (ref "R41") (pin "1") (pinfunction "1_1") (pintype "passive"))
    )
    (net (code "58") (name "Net-(IC2A-QE)") (class "Default")
      (node (ref "IC2") (pin "4") (pinfunction "QE_4") (pintype "tri_state"))
      (node (ref "R40") (pin "1") (pinfunction "1_1") (pintype "passive"))
    )
    (net (code "59") (name "Net-(IC2A-QF)") (class "Default")
      (node (ref "IC2") (pin "5") (pinfunction "QF_5") (pintype "tri_state"))
      (node (ref "R39") (pin "1") (pinfunction "1_1") (pintype "passive"))
    )
    (net (code "60") (name "Net-(IC2A-QG)") (class "Default")
      (node (ref "IC2") (pin "6") (pinfunction "QG_6") (pintype "tri_state"))
      (node (ref "R38") (pin "1") (pinfunction "1_1") (pintype "passive"))
    )
    (net (code "61") (name "Net-(IC3-ADJ)") (class "Default")
      (node (ref "IC3") (pin "1") (pinfunction "ADJ_1") (pintype "input"))
      (node (ref "R1") (pin "1") (pinfunction "1_1") (pintype "passive"))
      (node (ref "R2") (pin "2") (pinfunction "2_2") (pintype "passive"))
    )
    (net (code "62") (name "Net-(IC4-ADJ)") (class "Default")
      (node (ref "IC4") (pin "1") (pinfunction "ADJ_1") (pintype "input"))
      (node (ref "R3") (pin "1") (pinfunction "1_1") (pintype "passive"))
      (node (ref "R4") (pin "2") (pinfunction "2_2") (pintype "passive"))
    )
    (net (code "63") (name "Net-(LED1-PadA)") (class "Default")
      (node (ref "LED1") (pin "A") (pinfunction "A_A") (pintype "passive"))
      (node (ref "R19") (pin "1") (pinfunction "1_1") (pintype "passive"))
    )
    (net (code "64") (name "Net-(LED2-PadA)") (class "Default")
      (node (ref "LED2") (pin "A") (pinfunction "A_A") (pintype "passive"))
      (node (ref "R20") (pin "1") (pinfunction "1_1") (pintype "passive"))
    )
    (net (code "65") (name "Net-(LED3-PadA)") (class "Default")
      (node (ref "LED3") (pin "A") (pinfunction "A_A") (pintype "passive"))
      (node (ref "R21") (pin "1") (pinfunction "1_1") (pintype "passive"))
    )
    (net (code "66") (name "Net-(LED4-PadA)") (class "Default")
      (node (ref "LED4") (pin "A") (pinfunction "A_A") (pintype "passive"))
      (node (ref "R22") (pin "1") (pinfunction "1_1") (pintype "passive"))
    )
    (net (code "67") (name "Net-(LED5-PadA)") (class "Default")
      (node (ref "LED5") (pin "A") (pinfunction "A_A") (pintype "passive"))
      (node (ref "R23") (pin "1") (pinfunction "1_1") (pintype "passive"))
    )
    (net (code "68") (name "Net-(LED6-PadA)") (class "Default")
      (node (ref "LED6") (pin "A") (pinfunction "A_A") (pintype "passive"))
      (node (ref "R24") (pin "1") (pinfunction "1_1") (pintype "passive"))
    )
    (net (code "69") (name "Net-(LED7-PadA)") (class "Default")
      (node (ref "LED7") (pin "A") (pinfunction "A_A") (pintype "passive"))
      (node (ref "R25") (pin "1") (pinfunction "1_1") (pintype "passive"))
    )
    (net (code "70") (name "Net-(LED8-PadA)") (class "Default")
      (node (ref "LED8") (pin "A") (pinfunction "A_A") (pintype "passive"))
      (node (ref "R26") (pin "1") (pinfunction "1_1") (pintype "passive"))
    )
    (net (code "71") (name "Net-(LED9-PadA)") (class "Default")
      (node (ref "LED9") (pin "A") (pinfunction "A_A") (pintype "passive"))
      (node (ref "R29") (pin "1") (pinfunction "1_1") (pintype "passive"))
    )
    (net (code "72") (name "Net-(LED10-PadA)") (class "Default")
      (node (ref "LED10") (pin "A") (pinfunction "A_A") (pintype "passive"))
      (node (ref "R30") (pin "1") (pinfunction "1_1") (pintype "passive"))
    )
    (net (code "73") (name "Net-(S1-S1)") (class "Default")
      (node (ref "R11") (pin "1") (pinfunction "1_1") (pintype "passive"))
      (node (ref "S1") (pin "2") (pinfunction "S1_2") (pintype "passive"))
    )
    (net (code "74") (name "Net-(S2-S1)") (class "Default")
      (node (ref "R12") (pin "1") (pinfunction "1_1") (pintype "passive"))
      (node (ref "S2") (pin "2") (pinfunction "S1_2") (pintype "passive"))
    )
    (net (code "75") (name "Net-(S3-S1)") (class "Default")
      (node (ref "R13") (pin "1") (pinfunction "1_1") (pintype "passive"))
      (node (ref "S3") (pin "2") (pinfunction "S1_2") (pintype "passive"))
    )
    (net (code "76") (name "Net-(S4-S1)") (class "Default")
      (node (ref "R14") (pin "1") (pinfunction "1_1") (pintype "passive"))
      (node (ref "S4") (pin "2") (pinfunction "S1_2") (pintype "passive"))
    )
    (net (code "77") (name "Net-(S5-S1)") (class "Default")
      (node (ref "R15") (pin "1") (pinfunction "1_1") (pintype "passive"))
      (node (ref "S5") (pin "2") (pinfunction "S1_2") (pintype "passive"))
    )
    (net (code "78") (name "Net-(S6-S1)") (class "Default")
      (node (ref "R16") (pin "1") (pinfunction "1_1") (pintype "passive"))
      (node (ref "S6") (pin "2") (pinfunction "S1_2") (pintype "passive"))
    )
    (net (code "79") (name "Net-(S7-S1)") (class "Default")
      (node (ref "R17") (pin "1") (pinfunction "1_1") (pintype "passive"))
      (node (ref "S7") (pin "2") (pinfunction "S1_2") (pintype "passive"))
    )
    (net (code "80") (name "Net-(S8-S1)") (class "Default")
      (node (ref "R18") (pin "1") (pinfunction "1_1") (pintype "passive"))
      (node (ref "S8") (pin "2") (pinfunction "S1_2") (pintype "passive"))
    )
    (net (code "81") (name "Net-(X2-A)") (class "Default")
      (node (ref "R5") (pin "1") (pinfunction "1_1") (pintype "passive"))
      (node (ref "X2") (pin "15") (pinfunction "A_15") (pintype "input"))
    )
    (net (code "82") (name "Net-(X2-VO)") (class "Default")
      (node (ref "R27") (pin "S") (pinfunction "S_S") (pintype "passive"))
      (node (ref "X2") (pin "3") (pinfunction "VO_3") (pintype "input"))
    )
    (net (code "83") (name "PA0") (class "Default")
      (node (ref "JP3") (pin "4") (pinfunction "4_4") (pintype "passive"))
      (node (ref "U$1") (pin "P$75") (pinfunction "PA0_P$75") (pintype "bidirectional"))
    )
    (net (code "84") (name "PA1") (class "Default")
      (node (ref "JP3") (pin "3") (pinfunction "3_3") (pintype "passive"))
      (node (ref "U$1") (pin "P$76") (pinfunction "PA1_P$76") (pintype "bidirectional"))
    )
    (net (code "85") (name "PA2") (class "Default")
      (node (ref "JP3") (pin "2") (pinfunction "2_2") (pintype "passive"))
      (node (ref "U$1") (pin "P$77") (pinfunction "PA2_P$77") (pintype "bidirectional"))
    )
    (net (code "86") (name "PA9") (class "Default")
      (node (ref "IC1") (pin "12") (pinfunction "RCK_12") (pintype "input"))
      (node (ref "IC2") (pin "12") (pinfunction "RCK_12") (pintype "input"))
      (node (ref "JP3") (pin "1") (pinfunction "1_1") (pintype "passive"))
      (node (ref "U$1") (pin "P$40") (pinfunction "PA9_P$40") (pintype "bidirectional"))
    )
    (net (code "87") (name "PB4") (class "Default")
      (node (ref "JP3") (pin "18") (pinfunction "18_18") (pintype "passive"))
      (node (ref "U$1") (pin "P$54") (pinfunction "PB4_P$54") (pintype "bidirectional"))
    )
    (net (code "88") (name "PB9") (class "Default")
      (node (ref "JP3") (pin "17") (pinfunction "17_17") (pintype "passive"))
      (node (ref "U$1") (pin "P$59") (pinfunction "PB9_P$59") (pintype "bidirectional"))
    )
    (net (code "89") (name "PC0") (class "Default")
      (node (ref "JP3") (pin "8") (pinfunction "8_8") (pintype "passive"))
      (node (ref "U$1") (pin "P$71") (pinfunction "PC0_P$71") (pintype "bidirectional"))
    )
    (net (code "90") (name "PC1") (class "Default")
      (node (ref "JP3") (pin "7") (pinfunction "7_7") (pintype "passive"))
      (node (ref "U$1") (pin "P$72") (pinfunction "PC1_P$72") (pintype "bidirectional"))
    )
    (net (code "91") (name "PC2") (class "Default")
      (node (ref "JP3") (pin "6") (pinfunction "6_6") (pintype "passive"))
      (node (ref "U$1") (pin "P$73") (pinfunction "PC2_P$73") (pintype "bidirectional"))
    )
    (net (code "92") (name "PC3") (class "Default")
      (node (ref "JP3") (pin "5") (pinfunction "5_5") (pintype "passive"))
      (node (ref "U$1") (pin "P$74") (pinfunction "PC3_P$74") (pintype "bidirectional"))
    )
    (net (code "93") (name "PC13") (class "Default")
      (node (ref "JP3") (pin "9") (pinfunction "9_9") (pintype "passive"))
      (node (ref "U$1") (pin "P$68") (pinfunction "PC13_P$68") (pintype "bidirectional"))
    )
    (net (code "94") (name "PD4") (class "Default")
      (node (ref "JP3") (pin "20") (pinfunction "20_20") (pintype "passive"))
      (node (ref "U$1") (pin "P$50") (pinfunction "PD4_P$50") (pintype "bidirectional"))
    )
    (net (code "95") (name "PD7") (class "Default")
      (node (ref "JP3") (pin "19") (pinfunction "19_19") (pintype "passive"))
      (node (ref "U$1") (pin "P$53") (pinfunction "PD7_P$53") (pintype "bidirectional"))
    )
    (net (code "96") (name "PE0") (class "Default")
      (node (ref "JP3") (pin "16") (pinfunction "16_16") (pintype "passive"))
      (node (ref "U$1") (pin "P$60") (pinfunction "PE0_P$60") (pintype "bidirectional"))
    )
    (net (code "97") (name "PE1") (class "Default")
      (node (ref "JP3") (pin "15") (pinfunction "15_15") (pintype "passive"))
      (node (ref "U$1") (pin "P$61") (pinfunction "PE1_P$61") (pintype "bidirectional"))
    )
    (net (code "98") (name "PE2") (class "Default")
      (node (ref "JP3") (pin "14") (pinfunction "14_14") (pintype "passive"))
      (node (ref "U$1") (pin "P$63") (pinfunction "PE2_P$63") (pintype "bidirectional"))
    )
    (net (code "99") (name "PE3") (class "Default")
      (node (ref "JP3") (pin "13") (pinfunction "13_13") (pintype "passive"))
      (node (ref "U$1") (pin "P$64") (pinfunction "PE3_P$64") (pintype "bidirectional"))
    )
    (net (code "100") (name "PE4") (class "Default")
      (node (ref "JP3") (pin "12") (pinfunction "12_12") (pintype "passive"))
      (node (ref "U$1") (pin "P$65") (pinfunction "PE4_P$65") (pintype "bidirectional"))
    )
    (net (code "101") (name "PE5") (class "Default")
      (node (ref "JP3") (pin "11") (pinfunction "11_11") (pintype "passive"))
      (node (ref "U$1") (pin "P$66") (pinfunction "PE5_P$66") (pintype "bidirectional"))
    )
    (net (code "102") (name "PE6") (class "Default")
      (node (ref "JP3") (pin "10") (pinfunction "10_10") (pintype "passive"))
      (node (ref "U$1") (pin "P$67") (pinfunction "PE6_P$67") (pintype "bidirectional"))
    )
    (net (code "103") (name "RS") (class "Default")
      (node (ref "U$1") (pin "P$24") (pinfunction "PB13_P$24") (pintype "bidirectional"))
      (node (ref "X2") (pin "4") (pinfunction "RS_4") (pintype "input"))
    )
    (net (code "104") (name "RW") (class "Default")
      (node (ref "U$1") (pin "P$35") (pinfunction "PC6_P$35") (pintype "bidirectional"))
      (node (ref "X2") (pin "5") (pinfunction "RW_5") (pintype "input"))
    )
    (net (code "105") (name "SCL") (class "Default")
      (node (ref "SV4") (pin "2") (pinfunction "2_2") (pintype "passive"))
      (node (ref "U$1") (pin "P$58") (pinfunction "PB8_P$58") (pintype "bidirectional"))
      (node (ref "X9") (pin "3") (pinfunction "S_3") (pintype "passive"))
      (node (ref "X9") (pin "4") (pinfunction "S_4") (pintype "passive"))
    )
    (net (code "106") (name "SDA") (class "Default")
      (node (ref "SV4") (pin "1") (pinfunction "1_1") (pintype "passive"))
      (node (ref "U$1") (pin "P$57") (pinfunction "PB7_P$57") (pintype "bidirectional"))
      (node (ref "X9") (pin "5") (pinfunction "S_5") (pintype "passive"))
      (node (ref "X9") (pin "6") (pinfunction "S_6") (pintype "passive"))
    )
    (net (code "107") (name "SDIO_CK") (class "Default")
      (node (ref "U$1") (pin "P$47") (pinfunction "PC12_P$47") (pintype "bidirectional"))
      (node (ref "X3") (pin "5") (pinfunction "5_5") (pintype "passive"))
    )
    (net (code "108") (name "SDIO_CMD") (class "Default")
      (node (ref "R7") (pin "1") (pinfunction "1_1") (pintype "passive"))
      (node (ref "U$1") (pin "P$48") (pinfunction "PD2_P$48") (pintype "bidirectional"))
      (node (ref "X3") (pin "2") (pinfunction "2_2") (pintype "passive"))
    )
    (net (code "109") (name "SDIO_D0") (class "Default")
      (node (ref "R8") (pin "1") (pinfunction "1_1") (pintype "passive"))
      (node (ref "U$1") (pin "P$37") (pinfunction "PC8_P$37") (pintype "bidirectional"))
      (node (ref "X3") (pin "7") (pinfunction "7_7") (pintype "passive"))
    )
    (net (code "110") (name "SDIO_D1") (class "Default")
      (node (ref "R9") (pin "1") (pinfunction "1_1") (pintype "passive"))
      (node (ref "U$1") (pin "P$38") (pinfunction "PC9_P$38") (pintype "bidirectional"))
      (node (ref "X3") (pin "8") (pinfunction "8_8") (pintype "passive"))
    )
    (net (code "111") (name "SDIO_D2") (class "Default")
      (node (ref "R10") (pin "1") (pinfunction "1_1") (pintype "passive"))
      (node (ref "U$1") (pin "P$45") (pinfunction "PC10_P$45") (pintype "bidirectional"))
      (node (ref "X3") (pin "9") (pinfunction "9_9") (pintype "passive"))
    )
    (net (code "112") (name "SDIO_D3") (class "Default")
      (node (ref "R6") (pin "1") (pinfunction "1_1") (pintype "passive"))
      (node (ref "U$1") (pin "P$46") (pinfunction "PC11_P$46") (pintype "bidirectional"))
      (node (ref "X3") (pin "1") (pinfunction "1_1") (pintype "passive"))
    )
    (net (code "113") (name "SD_IN") (class "Default")
      (node (ref "U$1") (pin "P$49") (pinfunction "PD3_P$49") (pintype "bidirectional"))
      (node (ref "X3") (pin "SW1") (pinfunction "SW1_SW1") (pintype "passive"))
    )
    (net (code "114") (name "SPI_MISO") (class "Default")
      (node (ref "ISP1") (pin "1") (pinfunction "MISO_1") (pintype "input"))
      (node (ref "SV5") (pin "1") (pinfunction "1_1") (pintype "passive"))
      (node (ref "U$1") (pin "P$4") (pinfunction "PA6_P$4") (pintype "bidirectional"))
    )
    (net (code "115") (name "SPI_MOSI") (class "Default")
      (node (ref "IC1") (pin "14") (pinfunction "SER_14") (pintype "input"))
      (node (ref "ISP1") (pin "4") (pinfunction "MOSI_4") (pintype "output"))
      (node (ref "SV5") (pin "4") (pinfunction "4_4") (pintype "passive"))
      (node (ref "U$1") (pin "P$5") (pinfunction "PA7_P$5") (pintype "bidirectional"))
    )
    (net (code "116") (name "SPI_SCK") (class "Default")
      (node (ref "IC1") (pin "11") (pinfunction "SCK_11") (pintype "input"))
      (node (ref "IC2") (pin "11") (pinfunction "SCK_11") (pintype "input"))
      (node (ref "ISP1") (pin "3") (pinfunction "SCK_3") (pintype "output"))
      (node (ref "SV5") (pin "3") (pinfunction "3_3") (pintype "passive"))
      (node (ref "U$1") (pin "P$3") (pinfunction "PA5_P$3") (pintype "bidirectional"))
    )
    (net (code "117") (name "SW1") (class "Default")
      (node (ref "S1") (pin "1") (pinfunction "S_1") (pintype "passive"))
      (node (ref "U$1") (pin "P$11") (pinfunction "PE8_P$11") (pintype "bidirectional"))
    )
    (net (code "118") (name "SW2") (class "Default")
      (node (ref "S2") (pin "1") (pinfunction "S_1") (pintype "passive"))
      (node (ref "U$1") (pin "P$12") (pinfunction "PE9_P$12") (pintype "bidirectional"))
    )
    (net (code "119") (name "SW3") (class "Default")
      (node (ref "S3") (pin "1") (pinfunction "S_1") (pintype "passive"))
      (node (ref "U$1") (pin "P$13") (pinfunction "PE10_P$13") (pintype "bidirectional"))
    )
    (net (code "120") (name "SW4") (class "Default")
      (node (ref "S4") (pin "1") (pinfunction "S_1") (pintype "passive"))
      (node (ref "U$1") (pin "P$14") (pinfunction "PE11_P$14") (pintype "bidirectional"))
    )
    (net (code "121") (name "SW5") (class "Default")
      (node (ref "S5") (pin "1") (pinfunction "S_1") (pintype "passive"))
      (node (ref "U$1") (pin "P$15") (pinfunction "PE12_P$15") (pintype "bidirectional"))
    )
    (net (code "122") (name "SW6") (class "Default")
      (node (ref "S6") (pin "1") (pinfunction "S_1") (pintype "passive"))
      (node (ref "U$1") (pin "P$16") (pinfunction "PE13_P$16") (pintype "bidirectional"))
    )
    (net (code "123") (name "SW7") (class "Default")
      (node (ref "S7") (pin "1") (pinfunction "S_1") (pintype "passive"))
      (node (ref "U$1") (pin "P$17") (pinfunction "PE14_P$17") (pintype "bidirectional"))
    )
    (net (code "124") (name "SW8") (class "Default")
      (node (ref "S8") (pin "1") (pinfunction "S_1") (pintype "passive"))
      (node (ref "U$1") (pin "P$18") (pinfunction "PE15_P$18") (pintype "bidirectional"))
    )
    (net (code "125") (name "USART1_RX") (class "Default")
      (node (ref "SV2") (pin "2") (pinfunction "2_2") (pintype "passive"))
      (node (ref "U$1") (pin "P$20") (pinfunction "PB11_P$20") (pintype "bidirectional"))
      (node (ref "X4") (pin "3") (pinfunction "S_3") (pintype "passive"))
      (node (ref "X4") (pin "4") (pinfunction "S_4") (pintype "passive"))
    )
    (net (code "126") (name "USART1_TX") (class "Default")
      (node (ref "SV2") (pin "1") (pinfunction "1_1") (pintype "passive"))
      (node (ref "U$1") (pin "P$19") (pinfunction "PB10_P$19") (pintype "bidirectional"))
      (node (ref "X4") (pin "5") (pinfunction "S_5") (pintype "passive"))
      (node (ref "X4") (pin "6") (pinfunction "S_6") (pintype "passive"))
    )
    (net (code "127") (name "USART2_RX") (class "Default")
      (node (ref "SV3") (pin "2") (pinfunction "2_2") (pintype "passive"))
      (node (ref "U$1") (pin "P$52") (pinfunction "PD6_P$52") (pintype "bidirectional"))
      (node (ref "X8") (pin "3") (pinfunction "S_3") (pintype "passive"))
      (node (ref "X8") (pin "4") (pinfunction "S_4") (pintype "passive"))
    )
    (net (code "128") (name "USART2_TX") (class "Default")
      (node (ref "SV3") (pin "1") (pinfunction "1_1") (pintype "passive"))
      (node (ref "U$1") (pin "P$51") (pinfunction "PD5_P$51") (pintype "bidirectional"))
      (node (ref "X8") (pin "5") (pinfunction "S_5") (pintype "passive"))
      (node (ref "X8") (pin "6") (pinfunction "S_6") (pintype "passive"))
    )
    (net (code "129") (name "unconnected-(IC2A-QH*-Pad9)") (class "Default")
      (node (ref "IC2") (pin "9") (pinfunction "QH*_9") (pintype "tri_state"))
    )
    (net (code "130") (name "unconnected-(ISP1-RST-Pad5)") (class "Default")
      (node (ref "ISP1") (pin "5") (pinfunction "RST_5") (pintype "output"))
    )
    (net (code "131") (name "unconnected-(SV5-Pad5)") (class "Default")
      (node (ref "SV5") (pin "5") (pinfunction "5_5") (pintype "passive"))
    )
    (net (code "132") (name "unconnected-(X3-PadSW2)") (class "Default")
      (node (ref "X3") (pin "SW2") (pinfunction "SW2_SW2") (pintype "passive"))
    )
    (net (code "133") (name "unconnected-(X5-Pad1)") (class "Default")
      (node (ref "X5") (pin "1") (pinfunction "1_1") (pintype "passive"))
    )
  )
)
